# ProPrj_NERVA_Charger_2026-04-29.net
KiCad netlist of a schematic drawn in EasyEDA Pro
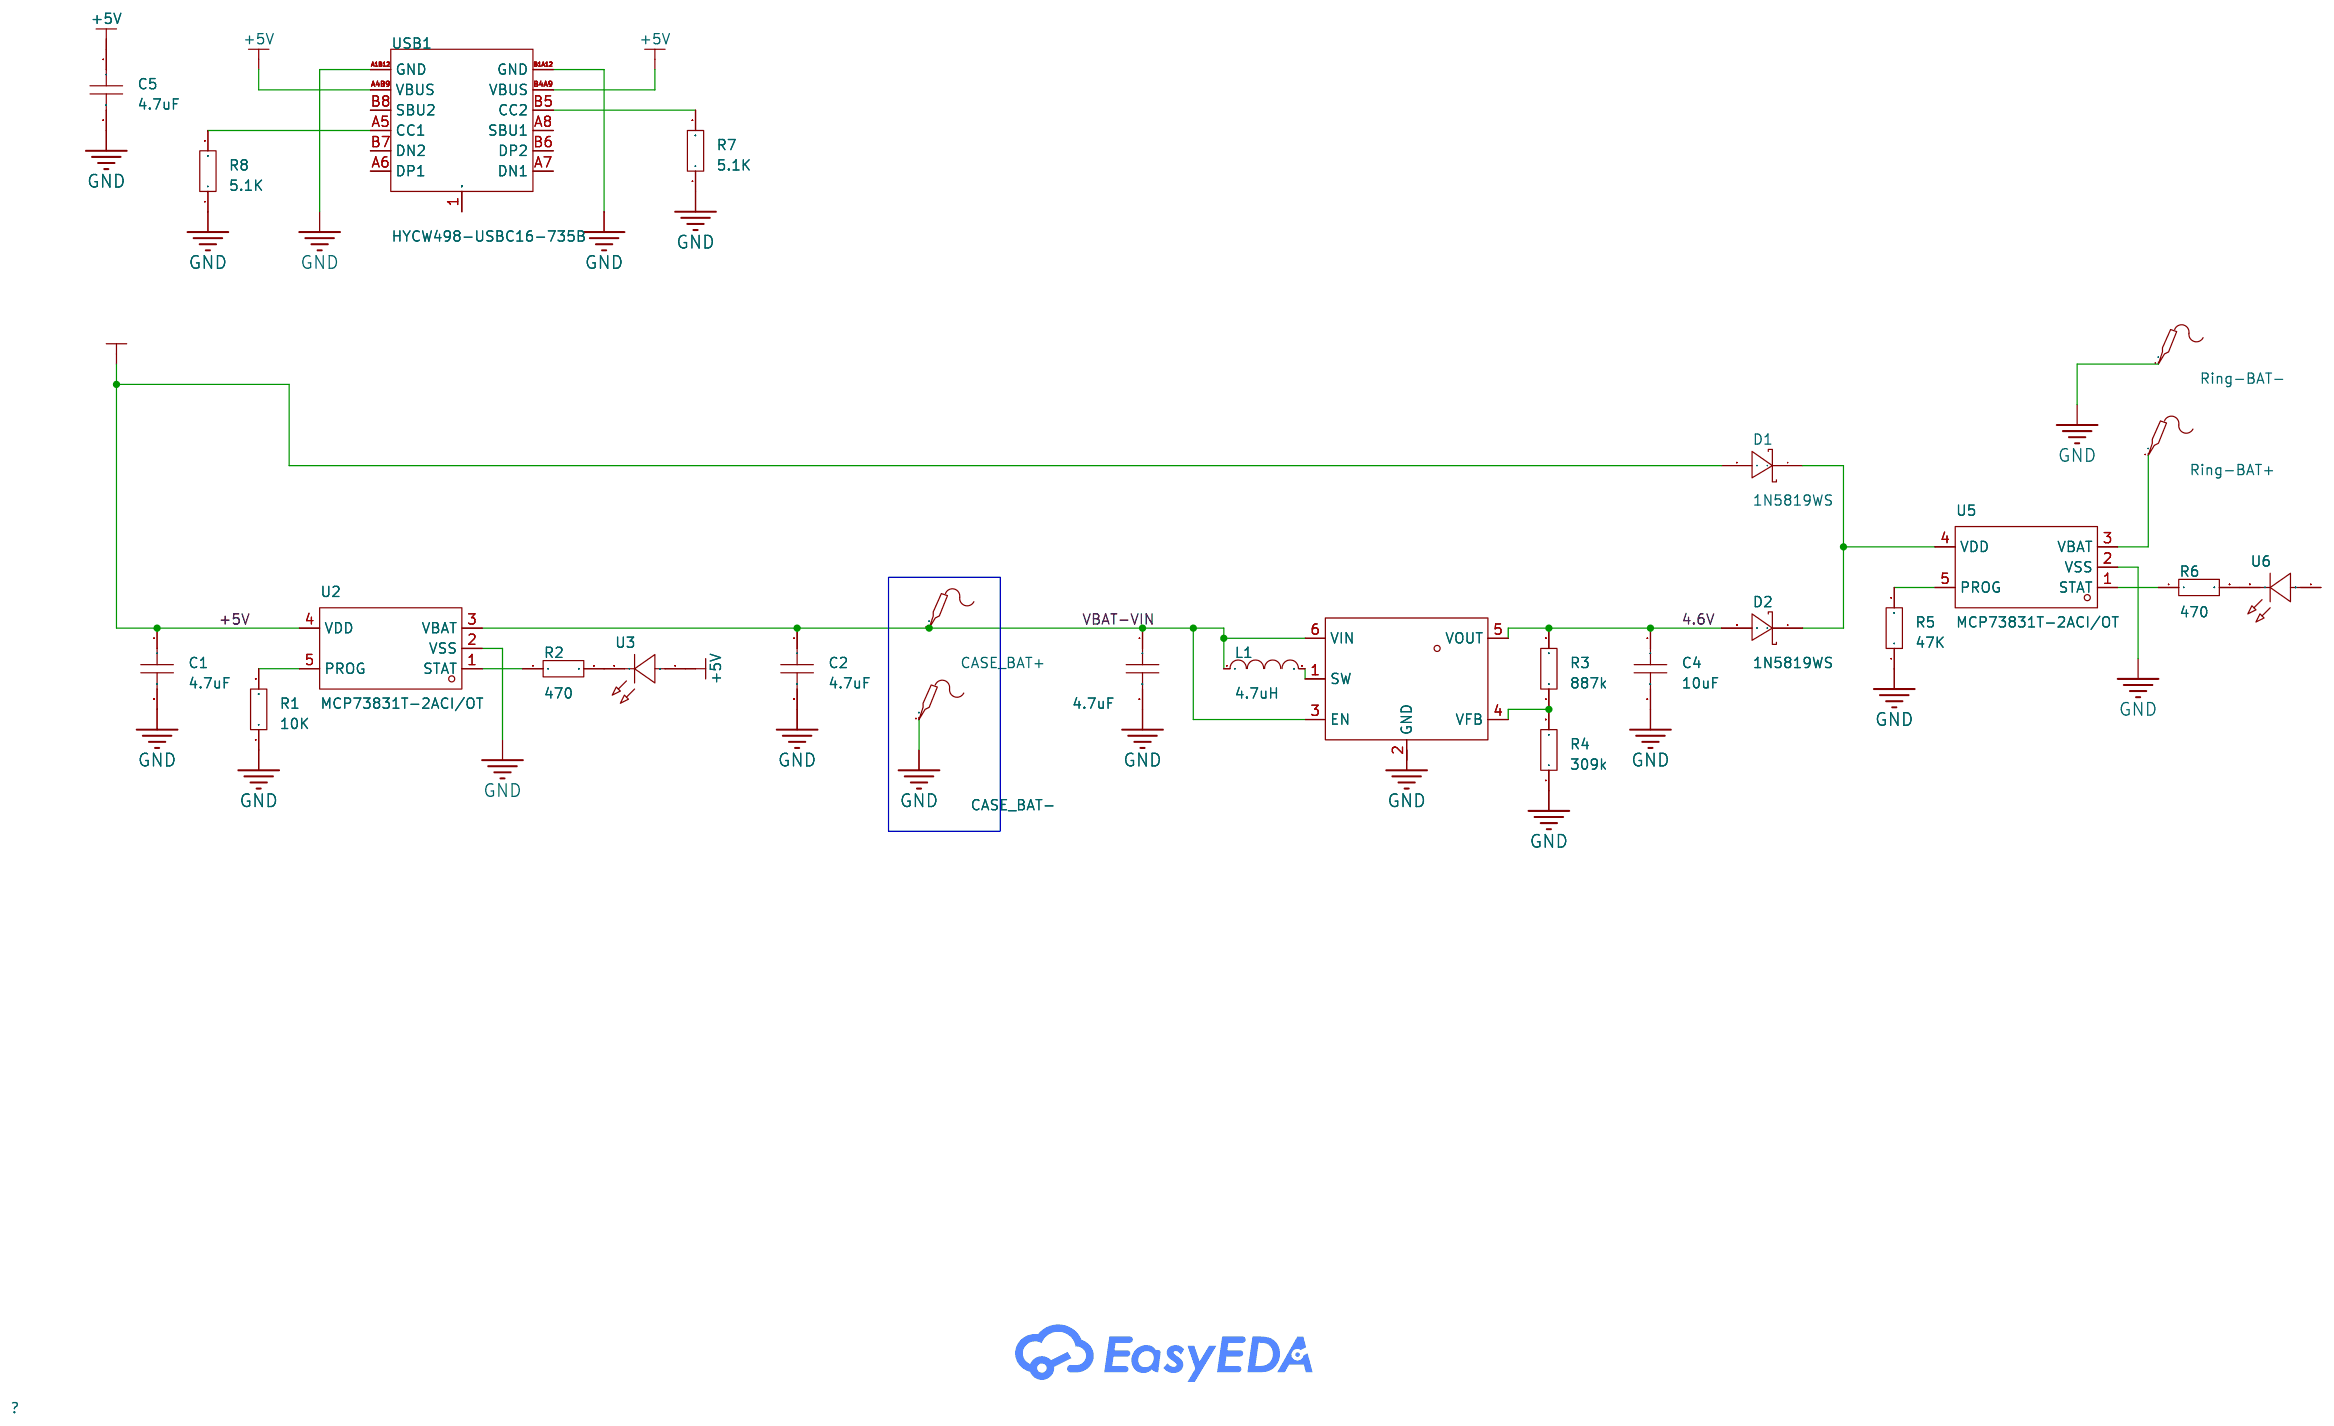
[diagram p0: schematic sheet]

(export (version "E")
  (design (tool "Eeschema 10.0.6"))
  (components
    (comp (ref "C1")
      (value "4.7uF")
      (footprint "easyedapro:C0603")
      (libsource (lib "easyedapro") (part "CAP"))
    )
    (comp (ref "C2")
      (value "4.7uF")
      (footprint "easyedapro:C0603")
      (libsource (lib "easyedapro") (part "CAP"))
    )
    (comp (ref "C3")
      (value "4.7uF")
      (footprint "easyedapro:C0603")
      (libsource (lib "easyedapro") (part "CAP"))
    )
    (comp (ref "C4")
      (value "10uF")
      (footprint "easyedapro:C0603")
      (libsource (lib "easyedapro") (part "CAP"))
    )
    (comp (ref "C5")
      (value "4.7uF")
      (footprint "easyedapro:C0603")
      (libsource (lib "easyedapro") (part "CAP"))
    )
    (comp (ref "CASE_BAT+")
      (value "~")
      (footprint "easyedapro:Test-Point-0.5mm")
      (description "Test Point 测试点")
      (libsource (lib "easyedapro") (part "Test-Point"))
    )
    (comp (ref "CASE_BAT-")
      (value "~")
      (footprint "easyedapro:Test-Point-0.5mm")
      (description "Test Point 测试点")
      (libsource (lib "easyedapro") (part "Test-Point"))
    )
    (comp (ref "D1")
      (value "1N5819WS")
      (footprint "easyedapro:SOD-323_L1.8-W1.3-LS2.5-RD")
      (fields (field (name "Manufacturer") "Hottech(合科泰)"))
      (libsource (lib "easyedapro") (part "1N5819WS"))
    )
    (comp (ref "D2")
      (value "1N5819WS")
      (footprint "easyedapro:SOD-323_L1.8-W1.3-LS2.5-RD")
      (fields (field (name "Manufacturer") "Hottech(合科泰)"))
      (libsource (lib "easyedapro") (part "1N5819WS"))
    )
    (comp (ref "L1")
      (value "4.7uH")
      (footprint "easyedapro:L0603")
      (libsource (lib "easyedapro") (part "电感"))
    )
    (comp (ref "R1") (value "10K") (footprint "easyedapro:R0603") (libsource (lib "easyedapro") (part "Res")))
    (comp (ref "R2") (value "470") (footprint "easyedapro:R0603") (libsource (lib "easyedapro") (part "Res")))
    (comp (ref "R3")
      (value "887k")
      (footprint "easyedapro:R0603")
      (libsource (lib "easyedapro") (part "Res"))
    )
    (comp (ref "R4")
      (value "309k")
      (footprint "easyedapro:R0603")
      (libsource (lib "easyedapro") (part "Res"))
    )
    (comp (ref "R5") (value "47K") (footprint "easyedapro:R0603") (libsource (lib "easyedapro") (part "Res")))
    (comp (ref "R6") (value "470") (footprint "easyedapro:R0603") (libsource (lib "easyedapro") (part "Res")))
    (comp (ref "R7")
      (value "5.1K")
      (footprint "easyedapro:R0603")
      (libsource (lib "easyedapro") (part "Res"))
    )
    (comp (ref "R8")
      (value "5.1K")
      (footprint "easyedapro:R0603")
      (libsource (lib "easyedapro") (part "Res"))
    )
    (comp (ref "Ring-BAT+")
      (value "~")
      (footprint "easyedapro:Test-Point-0.5mm")
      (description "Test Point 测试点")
      (libsource (lib "easyedapro") (part "Test-Point"))
    )
    (comp (ref "Ring-BAT-")
      (value "~")
      (footprint "easyedapro:Test-Point-0.5mm")
      (description "Test Point 测试点")
      (libsource (lib "easyedapro") (part "Test-Point"))
    )
    (comp (ref "U2")
      (value "MCP73831T-2ACI/OT")
      (footprint "easyedapro:SOT-23-5_L3.0-W1.7-P0.95-LS2.8-BL")
      (fields (field (name "Manufacturer") "MICROCHIP(美国微芯)"))
      (libsource (lib "easyedapro") (part "MCP73831T-2ACI/OT"))
    )
    (comp (ref "U3")
      (value "DY-5173URD/SN-A3(EL)(HF)")
      (footprint "easyedapro:LED-TH_L7.1-W2.4-FD")
      (fields (field (name "Manufacturer") "TONYU(东裕)"))
      (libsource (lib "easyedapro") (part "DY-5173URD/SN-A3(EL)(HF)"))
    )
    (comp (ref "U4")
      (value "MCP1640BT-I/CHY")
      (footprint "easyedapro:SOT-23-6_L2.9-W1.6-P0.95-LS2.8-BR")
      (fields (field (name "Manufacturer") "MICROCHIP(美国微芯)"))
      (libsource (lib "easyedapro") (part "MCP1640BT-I/CHY"))
    )
    (comp (ref "U5")
      (value "MCP73831T-2ACI/OT")
      (footprint "easyedapro:SOT-23-5_L3.0-W1.7-P0.95-LS2.8-BL")
      (fields (field (name "Manufacturer") "MICROCHIP(美国微芯)"))
      (libsource (lib "easyedapro") (part "MCP73831T-2ACI/OT"))
    )
    (comp (ref "U6")
      (value "DY-5173URD/SN-A3(EL)(HF)")
      (footprint "easyedapro:LED-TH_L7.1-W2.4-FD")
      (fields (field (name "Manufacturer") "TONYU(东裕)"))
      (libsource (lib "easyedapro") (part "DY-5173URD/SN-A3(EL)(HF)"))
    )
    (comp (ref "USB1")
      (value "HYCW498-USBC16-735B")
      (footprint "easyedapro:USB-C-SMD_HYCW498-USBC16-735B")
      (fields (field (name "Manufacturer") "华宇创"))
      (libsource (lib "easyedapro") (part "HYCW498-USBC16-735B"))
    )
  )
  (nets
    (net (code "1") (name "+5V") (class "Default")
      (node (ref "C1") (pin "1") (pinfunction "1_1") (pintype "input"))
      (node (ref "C5") (pin "1") (pinfunction "1_1") (pintype "input"))
      (node (ref "D1") (pin "2") (pinfunction "A_2") (pintype "unspecified"))
      (node (ref "U2") (pin "4") (pinfunction "VDD_4") (pintype "unspecified"))
      (node (ref "U3") (pin "1") (pinfunction "C_1") (pintype "unspecified"))
      (node (ref "USB1") (pin "A4B9") (pinfunction "VBUS_A4B9") (pintype "unspecified"))
      (node (ref "USB1") (pin "B4A9") (pinfunction "VBUS_B4A9") (pintype "unspecified"))
    )
    (net (code "2") (name "/4.6V") (class "Default")
      (node (ref "C4") (pin "1") (pinfunction "1_1") (pintype "input"))
      (node (ref "D2") (pin "2") (pinfunction "A_2") (pintype "unspecified"))
      (node (ref "R3") (pin "2") (pinfunction "2_2") (pintype "input"))
      (node (ref "U4") (pin "5") (pinfunction "VOUT_5") (pintype "input"))
    )
    (net (code "3") (name "/VBAT-VIN") (class "Default")
      (node (ref "C2") (pin "1") (pinfunction "1_1") (pintype "input"))
      (node (ref "C3") (pin "1") (pinfunction "1_1") (pintype "input"))
      (node (ref "CASE_BAT+") (pin "1") (pinfunction "1_1") (pintype "unspecified"))
      (node (ref "L1") (pin "1") (pinfunction "1_1") (pintype "input"))
      (node (ref "U2") (pin "3") (pinfunction "VBAT_3") (pintype "unspecified"))
      (node (ref "U4") (pin "3") (pinfunction "EN_3") (pintype "input"))
      (node (ref "U4") (pin "6") (pinfunction "VIN_6") (pintype "input"))
    )
    (net (code "4") (name "GND") (class "Default")
      (node (ref "C1") (pin "2") (pinfunction "2_2") (pintype "input"))
      (node (ref "C2") (pin "2") (pinfunction "2_2") (pintype "input"))
      (node (ref "C3") (pin "2") (pinfunction "2_2") (pintype "input"))
      (node (ref "C4") (pin "2") (pinfunction "2_2") (pintype "input"))
      (node (ref "C5") (pin "2") (pinfunction "2_2") (pintype "input"))
      (node (ref "CASE_BAT-") (pin "1") (pinfunction "1_1") (pintype "unspecified"))
      (node (ref "R1") (pin "1") (pinfunction "1_1") (pintype "input"))
      (node (ref "R4") (pin "1") (pinfunction "1_1") (pintype "input"))
      (node (ref "R5") (pin "1") (pinfunction "1_1") (pintype "input"))
      (node (ref "R7") (pin "1") (pinfunction "1_1") (pintype "input"))
      (node (ref "R8") (pin "1") (pinfunction "1_1") (pintype "input"))
      (node (ref "Ring-BAT-") (pin "1") (pinfunction "1_1") (pintype "unspecified"))
      (node (ref "U2") (pin "2") (pinfunction "VSS_2") (pintype "unspecified"))
      (node (ref "U4") (pin "2") (pinfunction "GND_2") (pintype "input"))
      (node (ref "U5") (pin "2") (pinfunction "VSS_2") (pintype "unspecified"))
      (node (ref "USB1") (pin "A1B12") (pinfunction "GND_A1B12") (pintype "unspecified"))
      (node (ref "USB1") (pin "B1A12") (pinfunction "GND_B1A12") (pintype "unspecified"))
    )
    (net (code "5") (name "Net-(D1-K)") (class "Default")
      (node (ref "D1") (pin "1") (pinfunction "K_1") (pintype "unspecified"))
      (node (ref "D2") (pin "1") (pinfunction "K_1") (pintype "unspecified"))
      (node (ref "U5") (pin "4") (pinfunction "VDD_4") (pintype "unspecified"))
    )
    (net (code "6") (name "Net-(U2-PROG)") (class "Default")
      (node (ref "R1") (pin "2") (pinfunction "2_2") (pintype "input"))
      (node (ref "U2") (pin "5") (pinfunction "PROG_5") (pintype "unspecified"))
    )
    (net (code "7") (name "Net-(U2-STAT)") (class "Default")
      (node (ref "R2") (pin "1") (pinfunction "1_1") (pintype "input"))
      (node (ref "U2") (pin "1") (pinfunction "STAT_1") (pintype "unspecified"))
    )
    (net (code "8") (name "Net-(U3-A)") (class "Default")
      (node (ref "R2") (pin "2") (pinfunction "2_2") (pintype "input"))
      (node (ref "U3") (pin "2") (pinfunction "A_2") (pintype "unspecified"))
    )
    (net (code "9") (name "Net-(U4-SW)") (class "Default")
      (node (ref "L1") (pin "2") (pinfunction "2_2") (pintype "input"))
      (node (ref "U4") (pin "1") (pinfunction "SW_1") (pintype "input"))
    )
    (net (code "10") (name "Net-(U4-VFB)") (class "Default")
      (node (ref "R3") (pin "1") (pinfunction "1_1") (pintype "input"))
      (node (ref "R4") (pin "2") (pinfunction "2_2") (pintype "input"))
      (node (ref "U4") (pin "4") (pinfunction "VFB_4") (pintype "input"))
    )
    (net (code "11") (name "Net-(U5-PROG)") (class "Default")
      (node (ref "R5") (pin "2") (pinfunction "2_2") (pintype "input"))
      (node (ref "U5") (pin "5") (pinfunction "PROG_5") (pintype "unspecified"))
    )
    (net (code "12") (name "Net-(U5-STAT)") (class "Default")
      (node (ref "R6") (pin "1") (pinfunction "1_1") (pintype "input"))
      (node (ref "U5") (pin "1") (pinfunction "STAT_1") (pintype "unspecified"))
    )
    (net (code "13") (name "Net-(U5-VBAT)") (class "Default")
      (node (ref "Ring-BAT+") (pin "1") (pinfunction "1_1") (pintype "unspecified"))
      (node (ref "U5") (pin "3") (pinfunction "VBAT_3") (pintype "unspecified"))
    )
    (net (code "14") (name "Net-(U6-A)") (class "Default")
      (node (ref "R6") (pin "2") (pinfunction "2_2") (pintype "input"))
      (node (ref "U6") (pin "2") (pinfunction "A_2") (pintype "unspecified"))
    )
    (net (code "15") (name "Net-(USB1-CC1)") (class "Default")
      (node (ref "R8") (pin "2") (pinfunction "2_2") (pintype "input"))
      (node (ref "USB1") (pin "A5") (pinfunction "CC1_A5") (pintype "unspecified"))
    )
    (net (code "16") (name "Net-(USB1-CC2)") (class "Default")
      (node (ref "R7") (pin "2") (pinfunction "2_2") (pintype "input"))
      (node (ref "USB1") (pin "B5") (pinfunction "CC2_B5") (pintype "unspecified"))
    )
    (net (code "17") (name "unconnected-(U6-C-Pad1)") (class "Default")
      (node (ref "U6") (pin "1") (pinfunction "C_1") (pintype "unspecified"))
    )
    (net (code "18") (name "unconnected-(USB1-DN1-PadA7)") (class "Default")
      (node (ref "USB1") (pin "A7") (pinfunction "DN1_A7") (pintype "unspecified"))
    )
    (net (code "19") (name "unconnected-(USB1-DN2-PadB7)") (class "Default")
      (node (ref "USB1") (pin "B7") (pinfunction "DN2_B7") (pintype "unspecified"))
    )
    (net (code "20") (name "unconnected-(USB1-DP1-PadA6)") (class "Default")
      (node (ref "USB1") (pin "A6") (pinfunction "DP1_A6") (pintype "unspecified"))
    )
    (net (code "21") (name "unconnected-(USB1-DP2-PadB6)") (class "Default")
      (node (ref "USB1") (pin "B6") (pinfunction "DP2_B6") (pintype "unspecified"))
    )
    (net (code "22") (name "unconnected-(USB1-SBU1-PadA8)") (class "Default")
      (node (ref "USB1") (pin "A8") (pinfunction "SBU1_A8") (pintype "unspecified"))
    )
    (net (code "23") (name "unconnected-(USB1-SBU2-PadB8)") (class "Default")
      (node (ref "USB1") (pin "B8") (pinfunction "SBU2_B8") (pintype "unspecified"))
    )
    (net (code "24") (name "unconnected-(USB1-SHELL-Pad1)") (class "Default")
      (node (ref "USB1") (pin "1") (pinfunction "SHELL_1") (pintype "unspecified"))
    )
  )
)
